# High_Side_FETs.net
KiCad netlist of a schematic drawn in Altium Designer
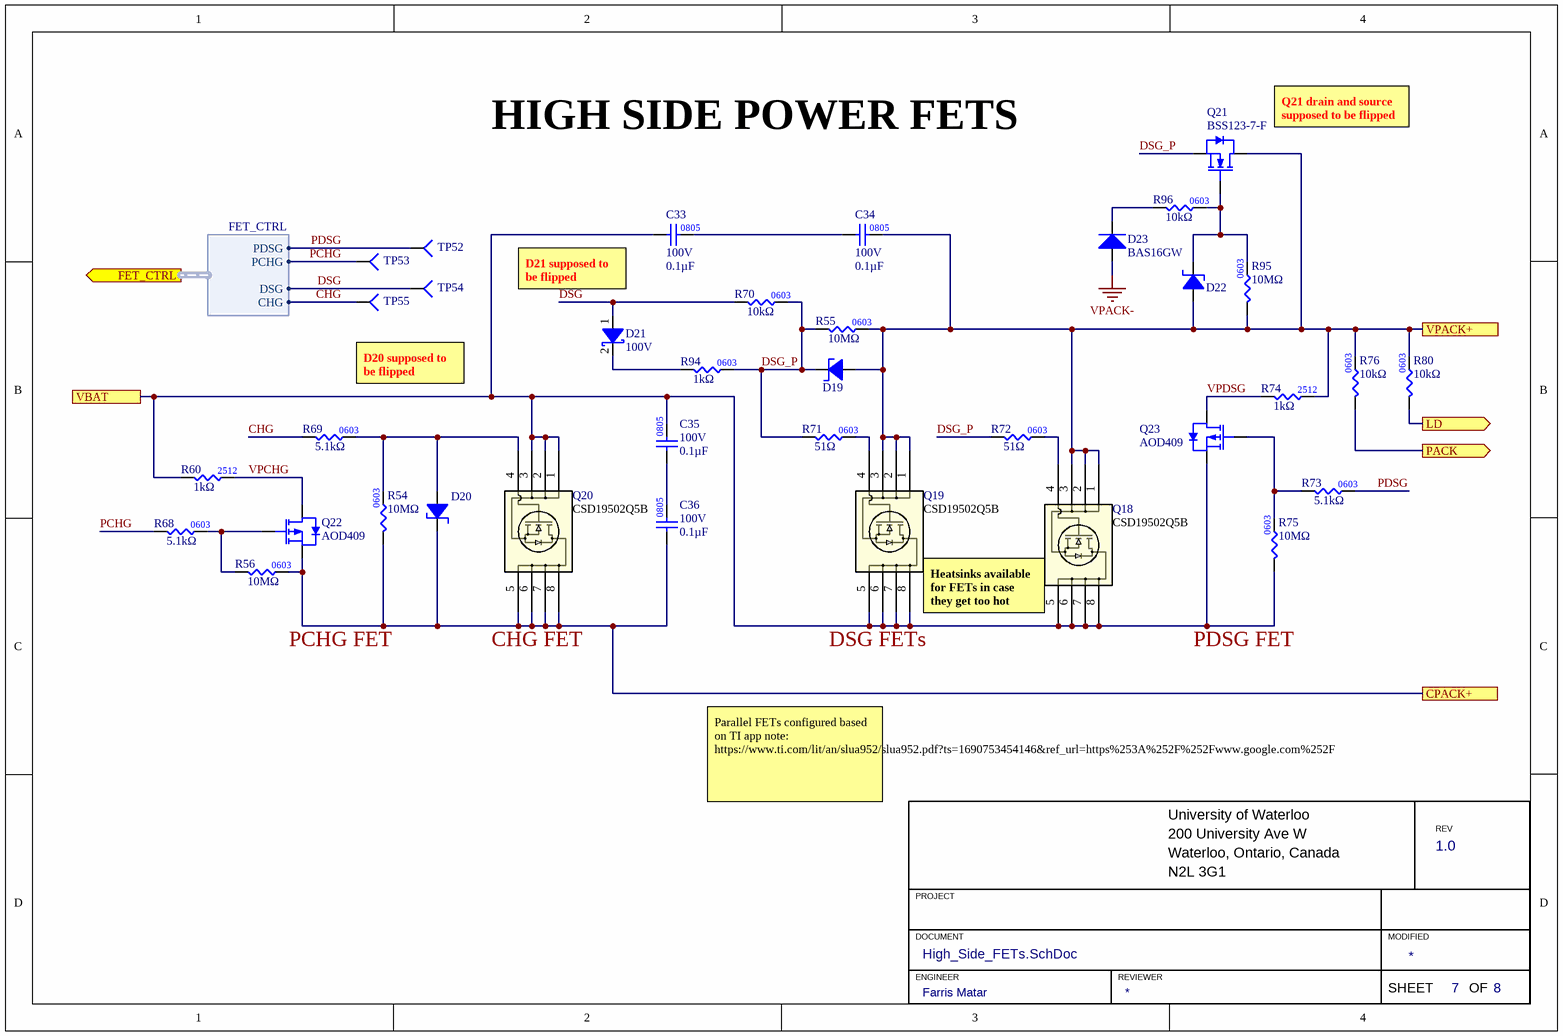
[diagram p0: High_Side_FETs.SchDoc]

(export (version "E")
  (design (tool "Eeschema 10.0.6"))
  (components
    (comp (ref "C33")
      (value "0.1µF")
      (footprint "CAP0805")
      (description "CAP CER 0.1UF 100V X7R 0805")
      (fields (field (name "VOLTAGE RATING") "100V") (field (name "Comment") "CAP_0.1uF_100V_0805"))
      (libsource (lib "Personal_Schematic_Library_2022") (part "CAP_0.1uF_100V_0805"))
    )
    (comp (ref "C34")
      (value "0.1µF")
      (footprint "CAP0805")
      (description "CAP CER 0.1UF 100V X7R 0805")
      (fields (field (name "VOLTAGE RATING") "100V") (field (name "Comment") "CAP_0.1uF_100V_0805"))
      (libsource (lib "Personal_Schematic_Library_2022") (part "CAP_0.1uF_100V_0805"))
    )
    (comp (ref "C35")
      (value "0.1µF")
      (footprint "CAP0805")
      (description "CAP CER 0.1UF 100V X7R 0805")
      (fields (field (name "VOLTAGE RATING") "100V") (field (name "Comment") "CAP_0.1uF_100V_0805"))
      (libsource (lib "Personal_Schematic_Library_2022") (part "CAP_0.1uF_100V_0805"))
    )
    (comp (ref "C36")
      (value "0.1µF")
      (footprint "CAP0805")
      (description "CAP CER 0.1UF 100V X7R 0805")
      (fields (field (name "VOLTAGE RATING") "100V") (field (name "Comment") "CAP_0.1uF_100V_0805"))
      (libsource (lib "Personal_Schematic_Library_2022") (part "CAP_0.1uF_100V_0805"))
    )
    (comp (ref "D19")
      (value "DIO_ZENER_16V")
      (footprint "SOD-123_FLAT")
      (description "DIODE ZENER 16V 500MW SOD123")
      (libsource (lib "Personal_Schematic_Library_2022") (part "DIO_ZENER_16V"))
    )
    (comp (ref "D20")
      (value "DIO_ZENER_16V")
      (footprint "SOD-123_FLAT")
      (description "DIODE ZENER 16V 500MW SOD123")
      (libsource (lib "Personal_Schematic_Library_2022") (part "DIO_ZENER_16V"))
    )
    (comp (ref "D21")
      (value "DIO_SCHOTTKY_100V_1A")
      (footprint "SOD-123_FLAT")
      (description "DIODE SCHOTTKY 100V 1A SOD-123F")
      (fields (field (name "VR (MAX)") "100V"))
      (libsource (lib "Personal_Schematic_Library_2022") (part "DIO_SCHOTTKY_100V_1A"))
    )
    (comp (ref "D22")
      (value "DIO_ZENER_16V")
      (footprint "SOD-123_FLAT")
      (description "DIODE ZENER 16V 500MW SOD123")
      (libsource (lib "Personal_Schematic_Library_2022") (part "DIO_ZENER_16V"))
    )
    (comp (ref "D23")
      (value "DIO_100V_215mA")
      (footprint "DIODSOD-123")
      (description "DIODE GEN PURP 100V 215MA SOD123")
      (fields (field (name "MANUFACTURER PART NUMBER 1") "BAS16GW"))
      (libsource (lib "Personal_Schematic_Library_2022") (part "DIO_100V_215mA"))
    )
    (comp (ref "Q18")
      (value "CSD19502Q5B")
      (footprint "DFN5060")
      (description "MOSFET N-CH 80V 100A 8VSON")
      (fields (field (name "MANUFACTURER PART NUMBER 1") "CSD19502Q5B"))
      (libsource (lib "Personal_Schematic_Library_2022") (part "NMOS_CSD19502Q5B_80V_100A"))
    )
    (comp (ref "Q19")
      (value "CSD19502Q5B")
      (footprint "DFN5060")
      (description "MOSFET N-CH 80V 100A 8VSON")
      (fields (field (name "MANUFACTURER PART NUMBER 1") "CSD19502Q5B"))
      (libsource (lib "Personal_Schematic_Library_2022") (part "NMOS_CSD19502Q5B_80V_100A"))
    )
    (comp (ref "Q20")
      (value "CSD19502Q5B")
      (footprint "DFN5060")
      (description "MOSFET N-CH 80V 100A 8VSON")
      (fields (field (name "MANUFACTURER PART NUMBER 1") "CSD19502Q5B"))
      (libsource (lib "Personal_Schematic_Library_2022") (part "NMOS_CSD19502Q5B_80V_100A"))
    )
    (comp (ref "Q21")
      (value "NMOS_100V_170mA")
      (footprint "SOT23-3")
      (description "MOSFET N-CH 100V 170MA SOT23-3")
      (fields (field (name "MANUFACTURER PART NUMBER 1") "BSS123-7-F"))
      (libsource (lib "Personal_Schematic_Library_2022") (part "NMOS_100V_170mA"))
    )
    (comp (ref "Q22")
      (value "PMOS_60V_26A")
      (footprint "TO-252 AOSMD")
      (description "MOSFET P-CH 60V 26A TO252")
      (fields (field (name "MANUFACTURER PART NUMBER 1") "AOD409"))
      (libsource (lib "Personal_Schematic_Library_2022") (part "PMOS_60V_26A"))
    )
    (comp (ref "Q23")
      (value "PMOS_60V_26A")
      (footprint "TO-252 AOSMD")
      (description "MOSFET P-CH 60V 26A TO252")
      (fields (field (name "MANUFACTURER PART NUMBER 1") "AOD409"))
      (libsource (lib "Personal_Schematic_Library_2022") (part "PMOS_60V_26A"))
    )
    (comp (ref "R54")
      (value "10MΩ")
      (footprint "RES0603")
      (description "RES 10M OHM 1% 1/10W 0603")
      (fields (field (name "Comment") "RES_10MΩ_0603_1%"))
      (libsource (lib "Personal_Schematic_Library_2022") (part "RES_10MΩ_0603_1%"))
    )
    (comp (ref "R55")
      (value "10MΩ")
      (footprint "RES0603")
      (description "RES 10M OHM 1% 1/10W 0603")
      (fields (field (name "Comment") "RES_10MΩ_0603_1%"))
      (libsource (lib "Personal_Schematic_Library_2022") (part "RES_10MΩ_0603_1%"))
    )
    (comp (ref "R56")
      (value "10MΩ")
      (footprint "RES0603")
      (description "RES 10M OHM 1% 1/10W 0603")
      (fields (field (name "Comment") "RES_10MΩ_0603_1%"))
      (libsource (lib "Personal_Schematic_Library_2022") (part "RES_10MΩ_0603_1%"))
    )
    (comp (ref "R60")
      (value "1kΩ")
      (footprint "RES2512")
      (description "RES SMD 1K OHM 1% 3W 2512")
      (fields (field (name "Comment") "RES_1kΩ_2512_1%"))
      (libsource (lib "Personal_Schematic_Library_2022") (part "RES_1kΩ_2512_1%"))
    )
    (comp (ref "R68")
      (value "5.1kΩ")
      (footprint "RES0603")
      (description "RES 5.1K OHM 1% 1/10W 0603")
      (fields (field (name "Comment") "RES_5.1kΩ_0603_1%"))
      (libsource (lib "Personal_Schematic_Library_2022") (part "RES_5.1kΩ_0603_1%"))
    )
    (comp (ref "R69")
      (value "5.1kΩ")
      (footprint "RES0603")
      (description "RES 5.1K OHM 1% 1/10W 0603")
      (fields (field (name "Comment") "RES_5.1kΩ_0603_1%"))
      (libsource (lib "Personal_Schematic_Library_2022") (part "RES_5.1kΩ_0603_1%"))
    )
    (comp (ref "R70")
      (value "10kΩ")
      (footprint "RES0603")
      (description "RES 10K OHM 1% 1/8W 0603")
      (fields (field (name "Comment") "RES_10kΩ_0603_1%"))
      (libsource (lib "Personal_Schematic_Library_2022") (part "RES_10kΩ_0603_1%"))
    )
    (comp (ref "R71")
      (value "51Ω")
      (footprint "RES0603")
      (description "RES 51 OHM 1% 1/10W 0603")
      (fields (field (name "Comment") "RES_51Ω_0603_1%"))
      (libsource (lib "Personal_Schematic_Library_2022") (part "RES_51Ω_0603_1%"))
    )
    (comp (ref "R72")
      (value "51Ω")
      (footprint "RES0603")
      (description "RES 51 OHM 1% 1/10W 0603")
      (fields (field (name "Comment") "RES_51Ω_0603_1%"))
      (libsource (lib "Personal_Schematic_Library_2022") (part "RES_51Ω_0603_1%"))
    )
    (comp (ref "R73")
      (value "5.1kΩ")
      (footprint "RES0603")
      (description "RES 5.1K OHM 1% 1/10W 0603")
      (fields (field (name "Comment") "RES_5.1kΩ_0603_1%"))
      (libsource (lib "Personal_Schematic_Library_2022") (part "RES_5.1kΩ_0603_1%"))
    )
    (comp (ref "R74")
      (value "1kΩ")
      (footprint "RES2512")
      (description "RES SMD 1K OHM 1% 3W 2512")
      (fields (field (name "Comment") "RES_1kΩ_2512_1%"))
      (libsource (lib "Personal_Schematic_Library_2022") (part "RES_1kΩ_2512_1%"))
    )
    (comp (ref "R75")
      (value "10MΩ")
      (footprint "RES0603")
      (description "RES 10M OHM 1% 1/10W 0603")
      (fields (field (name "Comment") "RES_10MΩ_0603_1%"))
      (libsource (lib "Personal_Schematic_Library_2022") (part "RES_10MΩ_0603_1%"))
    )
    (comp (ref "R76")
      (value "10kΩ")
      (footprint "RES0603")
      (description "RES 10K OHM 1% 1/8W 0603")
      (fields (field (name "Comment") "RES_10kΩ_0603_1%"))
      (libsource (lib "Personal_Schematic_Library_2022") (part "RES_10kΩ_0603_1%"))
    )
    (comp (ref "R80")
      (value "10kΩ")
      (footprint "RES0603")
      (description "RES 10K OHM 1% 1/8W 0603")
      (fields (field (name "Comment") "RES_10kΩ_0603_1%"))
      (libsource (lib "Personal_Schematic_Library_2022") (part "RES_10kΩ_0603_1%"))
    )
    (comp (ref "R94")
      (value "1kΩ")
      (footprint "RES0603")
      (description "RES 1K OHM 1% 1/8W 0603")
      (fields (field (name "Comment") "RES_1kΩ_0603_1%"))
      (libsource (lib "Personal_Schematic_Library_2022") (part "RES_1kΩ_0603_1%"))
    )
    (comp (ref "R95")
      (value "10MΩ")
      (footprint "RES0603")
      (description "RES 10M OHM 1% 1/10W 0603")
      (fields (field (name "Comment") "RES_10MΩ_0603_1%"))
      (libsource (lib "Personal_Schematic_Library_2022") (part "RES_10MΩ_0603_1%"))
    )
    (comp (ref "R96")
      (value "10kΩ")
      (footprint "RES0603")
      (description "RES 10K OHM 1% 1/8W 0603")
      (fields (field (name "Comment") "RES_10kΩ_0603_1%"))
      (libsource (lib "Personal_Schematic_Library_2022") (part "RES_10kΩ_0603_1%"))
    )
    (comp (ref "TP52")
      (value "TESTPOINT_1MM_CIRCLE")
      (footprint "TESTPOINT_CIRCLE_1MM")
      (description "TESTPOINT 1MM CIRCLE")
      (libsource (lib "Personal_Schematic_Library_2022") (part "TESTPOINT_1MM_CIRCLE"))
    )
    (comp (ref "TP53")
      (value "TESTPOINT_1MM_CIRCLE")
      (footprint "TESTPOINT_CIRCLE_1MM")
      (description "TESTPOINT 1MM CIRCLE")
      (libsource (lib "Personal_Schematic_Library_2022") (part "TESTPOINT_1MM_CIRCLE"))
    )
    (comp (ref "TP54")
      (value "TESTPOINT_1MM_CIRCLE")
      (footprint "TESTPOINT_CIRCLE_1MM")
      (description "TESTPOINT 1MM CIRCLE")
      (libsource (lib "Personal_Schematic_Library_2022") (part "TESTPOINT_1MM_CIRCLE"))
    )
    (comp (ref "TP55")
      (value "TESTPOINT_1MM_CIRCLE")
      (footprint "TESTPOINT_CIRCLE_1MM")
      (description "TESTPOINT 1MM CIRCLE")
      (libsource (lib "Personal_Schematic_Library_2022") (part "TESTPOINT_1MM_CIRCLE"))
    )
  )
  (nets
    (net (code "2") (name "/CHG") (class "Default")
      (node (ref "R69") (pin "1") (pinfunction "1_1") (pintype "passive"))
      (node (ref "TP55") (pin "1") (pinfunction "=value_1") (pintype "passive"))
    )
    (net (code "3") (name "/CPACK+") (class "Default")
      (node (ref "C36") (pin "1") (pinfunction "1_1") (pintype "passive"))
      (node (ref "D20") (pin "2") (pinfunction "Cathode_2") (pintype "passive"))
      (node (ref "Q20") (pin "5") (pinfunction "D_5") (pintype "passive"))
      (node (ref "Q20") (pin "6") (pinfunction "D_6") (pintype "passive"))
      (node (ref "Q20") (pin "7") (pinfunction "D_7") (pintype "passive"))
      (node (ref "Q20") (pin "8") (pinfunction "D_8") (pintype "passive"))
      (node (ref "Q22") (pin "3") (pinfunction "Source_3") (pintype "passive"))
      (node (ref "R54") (pin "1") (pinfunction "1_1") (pintype "passive"))
      (node (ref "R56") (pin "2") (pinfunction "2_2") (pintype "passive"))
    )
    (net (code "4") (name "/DSG") (class "Default")
      (node (ref "D21") (pin "1") (pinfunction "Anode_1") (pintype "passive"))
      (node (ref "R70") (pin "1") (pinfunction "1_1") (pintype "passive"))
      (node (ref "TP54") (pin "1") (pinfunction "=value_1") (pintype "passive"))
    )
    (net (code "5") (name "/DSG_P") (class "Default")
      (node (ref "D19") (pin "2") (pinfunction "Cathode_2") (pintype "passive"))
      (node (ref "Q21") (pin "2") (pinfunction "SOURCE_2") (pintype "passive"))
      (node (ref "R55") (pin "1") (pinfunction "1_1") (pintype "passive"))
      (node (ref "R70") (pin "2") (pinfunction "2_2") (pintype "passive"))
      (node (ref "R71") (pin "1") (pinfunction "1_1") (pintype "passive"))
      (node (ref "R72") (pin "1") (pinfunction "1_1") (pintype "passive"))
      (node (ref "R94") (pin "2") (pinfunction "2_2") (pintype "passive"))
    )
    (net (code "6") (name "/LD") (class "Default")
      (node (ref "R80") (pin "1") (pinfunction "1_1") (pintype "passive"))
    )
    (net (code "7") (name "/PACK") (class "Default")
      (node (ref "R76") (pin "1") (pinfunction "1_1") (pintype "passive"))
    )
    (net (code "8") (name "/PCHG") (class "Default")
      (node (ref "R68") (pin "1") (pinfunction "1_1") (pintype "passive"))
      (node (ref "TP53") (pin "1") (pinfunction "=value_1") (pintype "passive"))
    )
    (net (code "9") (name "/PDSG") (class "Default")
      (node (ref "R73") (pin "2") (pinfunction "2_2") (pintype "passive"))
      (node (ref "TP52") (pin "1") (pinfunction "=value_1") (pintype "passive"))
    )
    (net (code "10") (name "/VBAT") (class "Default")
      (node (ref "C33") (pin "1") (pinfunction "1_1") (pintype "passive"))
      (node (ref "C35") (pin "2") (pinfunction "2_2") (pintype "passive"))
      (node (ref "Q18") (pin "5") (pinfunction "D_5") (pintype "passive"))
      (node (ref "Q18") (pin "6") (pinfunction "D_6") (pintype "passive"))
      (node (ref "Q18") (pin "7") (pinfunction "D_7") (pintype "passive"))
      (node (ref "Q18") (pin "8") (pinfunction "D_8") (pintype "passive"))
      (node (ref "Q19") (pin "5") (pinfunction "D_5") (pintype "passive"))
      (node (ref "Q19") (pin "6") (pinfunction "D_6") (pintype "passive"))
      (node (ref "Q19") (pin "7") (pinfunction "D_7") (pintype "passive"))
      (node (ref "Q19") (pin "8") (pinfunction "D_8") (pintype "passive"))
      (node (ref "Q20") (pin "1") (pinfunction "S_1") (pintype "passive"))
      (node (ref "Q20") (pin "2") (pinfunction "S_2") (pintype "passive"))
      (node (ref "Q20") (pin "3") (pinfunction "S_3") (pintype "passive"))
      (node (ref "Q23") (pin "3") (pinfunction "Source_3") (pintype "passive"))
      (node (ref "R60") (pin "1") (pinfunction "1_1") (pintype "passive"))
      (node (ref "R75") (pin "1") (pinfunction "1_1") (pintype "passive"))
    )
    (net (code "11") (name "/VPACK+") (class "Default")
      (node (ref "C34") (pin "2") (pinfunction "2_2") (pintype "passive"))
      (node (ref "D19") (pin "1") (pinfunction "Anode_1") (pintype "passive"))
      (node (ref "D22") (pin "1") (pinfunction "Anode_1") (pintype "passive"))
      (node (ref "Q18") (pin "1") (pinfunction "S_1") (pintype "passive"))
      (node (ref "Q18") (pin "2") (pinfunction "S_2") (pintype "passive"))
      (node (ref "Q18") (pin "3") (pinfunction "S_3") (pintype "passive"))
      (node (ref "Q19") (pin "1") (pinfunction "S_1") (pintype "passive"))
      (node (ref "Q19") (pin "2") (pinfunction "S_2") (pintype "passive"))
      (node (ref "Q19") (pin "3") (pinfunction "S_3") (pintype "passive"))
      (node (ref "Q21") (pin "3") (pinfunction "DRAIN_3") (pintype "passive"))
      (node (ref "R55") (pin "2") (pinfunction "2_2") (pintype "passive"))
      (node (ref "R74") (pin "2") (pinfunction "2_2") (pintype "passive"))
      (node (ref "R76") (pin "2") (pinfunction "2_2") (pintype "passive"))
      (node (ref "R80") (pin "2") (pinfunction "2_2") (pintype "passive"))
      (node (ref "R95") (pin "1") (pinfunction "1_1") (pintype "passive"))
    )
    (net (code "12") (name "/VPCHG") (class "Default")
      (node (ref "Q22") (pin "2") (pinfunction "Drain_2") (pintype "passive"))
      (node (ref "R60") (pin "2") (pinfunction "2_2") (pintype "passive"))
    )
    (net (code "13") (name "/VPDSG") (class "Default")
      (node (ref "Q23") (pin "2") (pinfunction "Drain_2") (pintype "passive"))
      (node (ref "R74") (pin "1") (pinfunction "1_1") (pintype "passive"))
    )
    (net (code "15") (name "Net-(C33-Pad2)") (class "Default")
      (node (ref "C33") (pin "2") (pinfunction "2_2") (pintype "passive"))
      (node (ref "C34") (pin "1") (pinfunction "1_1") (pintype "passive"))
    )
    (net (code "16") (name "Net-(C35-Pad1)") (class "Default")
      (node (ref "C35") (pin "1") (pinfunction "1_1") (pintype "passive"))
      (node (ref "C36") (pin "2") (pinfunction "2_2") (pintype "passive"))
    )
    (net (code "17") (name "Net-(D20-Anode)") (class "Default")
      (node (ref "D20") (pin "1") (pinfunction "Anode_1") (pintype "passive"))
      (node (ref "Q20") (pin "4") (pinfunction "G_4") (pintype "passive"))
      (node (ref "R54") (pin "2") (pinfunction "2_2") (pintype "passive"))
      (node (ref "R69") (pin "2") (pinfunction "2_2") (pintype "passive"))
    )
    (net (code "18") (name "Net-(D21-Cathode)") (class "Default")
      (node (ref "D21") (pin "2") (pinfunction "Cathode_2") (pintype "passive"))
      (node (ref "R94") (pin "1") (pinfunction "1_1") (pintype "passive"))
    )
    (net (code "19") (name "Net-(D22-Cathode)") (class "Default")
      (node (ref "D22") (pin "2") (pinfunction "Cathode_2") (pintype "passive"))
      (node (ref "Q21") (pin "1") (pinfunction "GATE_1") (pintype "passive"))
      (node (ref "R95") (pin "2") (pinfunction "2_2") (pintype "passive"))
      (node (ref "R96") (pin "2") (pinfunction "2_2") (pintype "passive"))
    )
    (net (code "20") (name "Net-(D23-K)") (class "Default")
      (node (ref "D23") (pin "2") (pinfunction "K_2") (pintype "passive"))
      (node (ref "R96") (pin "1") (pinfunction "1_1") (pintype "passive"))
    )
    (net (code "21") (name "Net-(Q18-G)") (class "Default")
      (node (ref "Q18") (pin "4") (pinfunction "G_4") (pintype "passive"))
      (node (ref "R72") (pin "2") (pinfunction "2_2") (pintype "passive"))
    )
    (net (code "22") (name "Net-(Q19-G)") (class "Default")
      (node (ref "Q19") (pin "4") (pinfunction "G_4") (pintype "passive"))
      (node (ref "R71") (pin "2") (pinfunction "2_2") (pintype "passive"))
    )
    (net (code "23") (name "Net-(Q22-Gate)") (class "Default")
      (node (ref "Q22") (pin "1") (pinfunction "Gate_1") (pintype "passive"))
      (node (ref "R56") (pin "1") (pinfunction "1_1") (pintype "passive"))
      (node (ref "R68") (pin "2") (pinfunction "2_2") (pintype "passive"))
    )
    (net (code "24") (name "Net-(Q23-Gate)") (class "Default")
      (node (ref "Q23") (pin "1") (pinfunction "Gate_1") (pintype "passive"))
      (node (ref "R73") (pin "1") (pinfunction "1_1") (pintype "passive"))
      (node (ref "R75") (pin "2") (pinfunction "2_2") (pintype "passive"))
    )
    (net (code "25") (name "VPACK-") (class "Default")
      (node (ref "D23") (pin "1") (pinfunction "A_1") (pintype "passive"))
    )
  )
)
